# 2d_list_1.net
KiCad netlist of a schematic drawn in Altium Designer
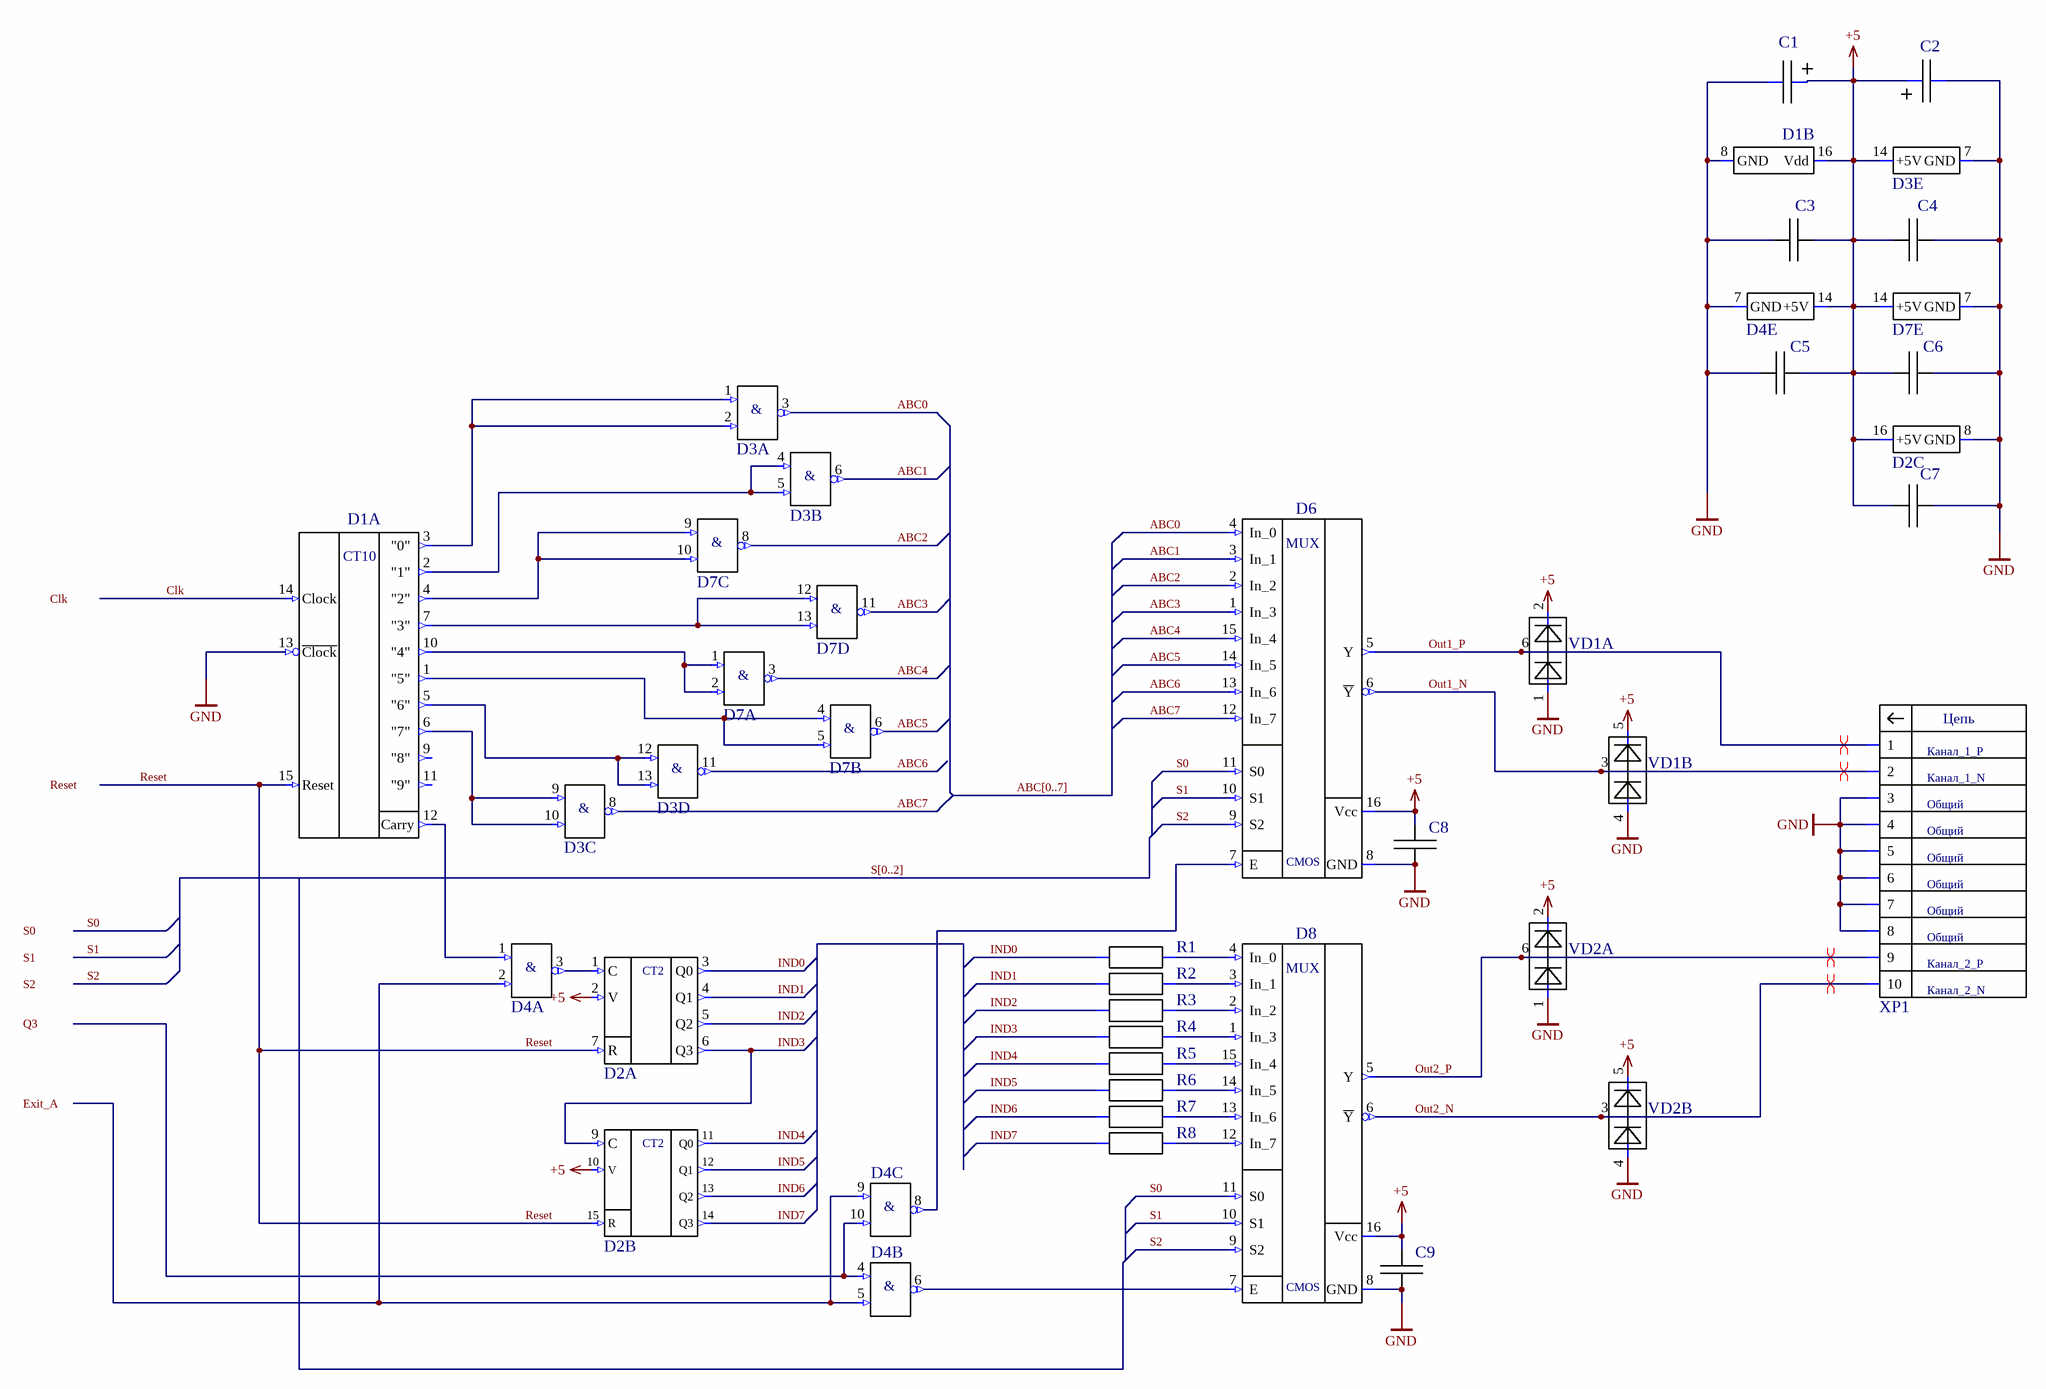
[diagram p0: 2d_list_1.schdoc]

(export (version "E")
  (design (tool "Eeschema 10.0.6"))
  (components
    (comp (ref "C1")
      (value "C")
      (footprint "C-Tantal")
      (description "К53-65 Конденсатор танталовый C(6032) 0,47-100 мкФ")
      (fields
        (field (name "MANUFACTURER") "ОАО \"Элеконд\"")
        (field (name "TOLERANCE") "10%")
        (field (name "CREATED_BY") "Желобаев")
      )
      (libsource (lib "Int_Library_for_Lessons_3") (part "K53-65_C_10%"))
    )
    (comp (ref "C2")
      (value "C")
      (footprint "C-Tantal")
      (description "К53-65 Конденсатор танталовый C(6032) 0,47-100 мкФ")
      (fields
        (field (name "MANUFACTURER") "ОАО \"Элеконд\"")
        (field (name "TOLERANCE") "10%")
        (field (name "CREATED_BY") "Желобаев")
      )
      (libsource (lib "Int_Library_for_Lessons_3") (part "K53-65_C_10%"))
    )
    (comp (ref "C3")
      (value "1206")
      (footprint "K10-79_3.2_1.6(1206)")
      (description "Чип конденсатор 1206 Н90 ряд Е6")
      (fields (field (name "MANUFACTURER") "ООО \"Кулон\"") (field (name "TOLERANCE") "+80%-20%"))
      (libsource (lib "Int_Library_for_Lessons_3") (part "К10-79_1206_Н90"))
    )
    (comp (ref "C4")
      (value "1206")
      (footprint "K10-79_3.2_1.6(1206)")
      (description "Чип конденсатор 1206 Н90 ряд Е6")
      (fields (field (name "MANUFACTURER") "ООО \"Кулон\"") (field (name "TOLERANCE") "+80%-20%"))
      (libsource (lib "Int_Library_for_Lessons_3") (part "К10-79_1206_Н90"))
    )
    (comp (ref "C5")
      (value "1206")
      (footprint "K10-79_3.2_1.6(1206)")
      (description "Чип конденсатор 1206 Н90 ряд Е6")
      (fields (field (name "MANUFACTURER") "ООО \"Кулон\"") (field (name "TOLERANCE") "+80%-20%"))
      (libsource (lib "Int_Library_for_Lessons_3") (part "К10-79_1206_Н90"))
    )
    (comp (ref "C6")
      (value "1206")
      (footprint "K10-79_3.2_1.6(1206)")
      (description "Чип конденсатор 1206 Н90 ряд Е6")
      (fields (field (name "MANUFACTURER") "ООО \"Кулон\"") (field (name "TOLERANCE") "+80%-20%"))
      (libsource (lib "Int_Library_for_Lessons_3") (part "К10-79_1206_Н90"))
    )
    (comp (ref "C7")
      (value "1206")
      (footprint "K10-79_3.2_1.6(1206)")
      (description "Чип конденсатор 1206 Н90 ряд Е6")
      (fields (field (name "MANUFACTURER") "ООО \"Кулон\"") (field (name "TOLERANCE") "+80%-20%"))
      (libsource (lib "Int_Library_for_Lessons_3") (part "К10-79_1206_Н90"))
    )
    (comp (ref "C8")
      (value "1206")
      (footprint "K10-79_3.2_1.6(1206)")
      (description "Чип конденсатор 1206 МП0 ряд Е24")
      (fields (field (name "MANUFACTURER") "ООО \"Кулон\"") (field (name "TOLERANCE") "±5%"))
      (libsource (lib "Int_Library_for_Lessons_3") (part "К10-79_1206_МП0"))
    )
    (comp (ref "C9")
      (value "1206")
      (footprint "K10-79_3.2_1.6(1206)")
      (description "Чип конденсатор 1206 МП0 ряд Е24")
      (fields (field (name "MANUFACTURER") "ООО \"Кулон\"") (field (name "TOLERANCE") "±5%"))
      (libsource (lib "Int_Library_for_Lessons_3") (part "К10-79_1206_МП0"))
    )
    (comp (ref "D1")
      (value "DIP-16")
      (footprint "DIP16")
      (description "Декадный счетчик c 10 декодированными выходами")
      (fields (field (name "MANUFACTURER") "STMicroelectronics") (field (name "CREATED_BY") "Желобаев"))
      (libsource (lib "Int_Library_for_Lessons_3") (part "HCF4017BEY"))
    )
    (comp (ref "D2")
      (value "~")
      (footprint "DIP16")
      (description "Два двоичных счетчика")
      (fields (field (name "MANUFACTURER") "Motorola") (field (name "CREATED_BY") "Желобаев"))
      (libsource (lib "Int_Library_for_Lessons_3") (part "MC14520BCP"))
    )
    (comp (ref "D3")
      (value "74AC00PC")
      (footprint "DIP14")
      (description "4 элемента 2И-НЕ TTL PDIP-14")
      (fields (field (name "MANUFACTURER") "ON Semiconductor") (field (name "CREATED_BY") "Желобаев"))
      (libsource (lib "Int_Library_for_Lessons_3") (part "74AC00PC"))
    )
    (comp (ref "D4")
      (value "74AC00PC")
      (footprint "DIP14")
      (description "4 элемента 2И-НЕ TTL PDIP-14")
      (fields (field (name "MANUFACTURER") "ON Semiconductor") (field (name "CREATED_BY") "Желобаев"))
      (libsource (lib "Int_Library_for_Lessons_3") (part "74AC00PC"))
    )
    (comp (ref "D6")
      (value "DIP-16")
      (footprint "DIP16")
      (description "мультиплексор 8 канальный CMOS")
      (fields (field (name "MANUFACTURER") "NXP Semiconductors") (field (name "CREATED_BY") "Желобаев"))
      (libsource (lib "Int_Library_for_Lessons_3") (part "74HC151N"))
    )
    (comp (ref "D7")
      (value "74AC00PC")
      (footprint "DIP14")
      (description "4 элемента 2И-НЕ TTL PDIP-14")
      (fields (field (name "MANUFACTURER") "ON Semiconductor") (field (name "CREATED_BY") "Желобаев"))
      (libsource (lib "Int_Library_for_Lessons_3") (part "74AC00PC"))
    )
    (comp (ref "D8")
      (value "DIP-16")
      (footprint "DIP16")
      (description "мультиплексор 8 канальный CMOS")
      (fields (field (name "MANUFACTURER") "NXP Semiconductors") (field (name "CREATED_BY") "Желобаев"))
      (libsource (lib "Int_Library_for_Lessons_3") (part "74HC151N"))
    )
    (comp (ref "R1")
      (value "~")
      (footprint "RES_0603_1608_N")
      (description "Резистор от 0,75 Ом до 10 МОм")
      (fields
        (field (name "MANUFACTURER") "ОАО \"НПО \"Эркон\"")
        (field (name "TOLERANCE") "5%")
        (field (name "CREATED_BY") "Желобаев")
      )
      (libsource (lib "Int_Library_for_Lessons_3") (part "Р1-12-0,1-5%"))
    )
    (comp (ref "R2")
      (value "~")
      (footprint "RES_0603_1608_N")
      (description "Резистор от 0,75 Ом до 10 МОм")
      (fields
        (field (name "MANUFACTURER") "ОАО \"НПО \"Эркон\"")
        (field (name "TOLERANCE") "5%")
        (field (name "CREATED_BY") "Желобаев")
      )
      (libsource (lib "Int_Library_for_Lessons_3") (part "Р1-12-0,1-5%"))
    )
    (comp (ref "R3")
      (value "~")
      (footprint "RES_0603_1608_N")
      (description "Резистор от 0,75 Ом до 10 МОм")
      (fields
        (field (name "MANUFACTURER") "ОАО \"НПО \"Эркон\"")
        (field (name "TOLERANCE") "5%")
        (field (name "CREATED_BY") "Желобаев")
      )
      (libsource (lib "Int_Library_for_Lessons_3") (part "Р1-12-0,1-5%"))
    )
    (comp (ref "R4")
      (value "~")
      (footprint "RES_0603_1608_N")
      (description "Резистор от 0,75 Ом до 10 МОм")
      (fields
        (field (name "MANUFACTURER") "ОАО \"НПО \"Эркон\"")
        (field (name "TOLERANCE") "5%")
        (field (name "CREATED_BY") "Желобаев")
      )
      (libsource (lib "Int_Library_for_Lessons_3") (part "Р1-12-0,1-5%"))
    )
    (comp (ref "R5")
      (value "~")
      (footprint "RES_0603_1608_N")
      (description "Резистор от 0,75 Ом до 10 МОм")
      (fields
        (field (name "MANUFACTURER") "ОАО \"НПО \"Эркон\"")
        (field (name "TOLERANCE") "5%")
        (field (name "CREATED_BY") "Желобаев")
      )
      (libsource (lib "Int_Library_for_Lessons_3") (part "Р1-12-0,1-5%"))
    )
    (comp (ref "R6")
      (value "~")
      (footprint "RES_0603_1608_N")
      (description "Резистор от 0,75 Ом до 10 МОм")
      (fields
        (field (name "MANUFACTURER") "ОАО \"НПО \"Эркон\"")
        (field (name "TOLERANCE") "5%")
        (field (name "CREATED_BY") "Желобаев")
      )
      (libsource (lib "Int_Library_for_Lessons_3") (part "Р1-12-0,1-5%"))
    )
    (comp (ref "R7")
      (value "~")
      (footprint "RES_0603_1608_N")
      (description "Резистор от 0,75 Ом до 10 МОм")
      (fields
        (field (name "MANUFACTURER") "ОАО \"НПО \"Эркон\"")
        (field (name "TOLERANCE") "5%")
        (field (name "CREATED_BY") "Желобаев")
      )
      (libsource (lib "Int_Library_for_Lessons_3") (part "Р1-12-0,1-5%"))
    )
    (comp (ref "R8")
      (value "~")
      (footprint "RES_0603_1608_N")
      (description "Резистор от 0,75 Ом до 10 МОм")
      (fields
        (field (name "MANUFACTURER") "ОАО \"НПО \"Эркон\"")
        (field (name "TOLERANCE") "5%")
        (field (name "CREATED_BY") "Желобаев")
      )
      (libsource (lib "Int_Library_for_Lessons_3") (part "Р1-12-0,1-5%"))
    )
    (comp (ref "VD1")
      (value "SOT-363")
      (footprint "SOT363_NXP")
      (description "Высокоскоростные, переключающие диоды")
      (fields
        (field (name "MANUFACTURER") "Nexperia")
        (field (name "VOLTAGE") "100")
        (field (name "CREATED_BY") "Желобаев")
      )
      (libsource (lib "Int_Library_for_Lessons_3") (part "BAV99S"))
    )
    (comp (ref "VD2")
      (value "SOT-363")
      (footprint "SOT363_NXP")
      (description "Высокоскоростные, переключающие диоды")
      (fields
        (field (name "MANUFACTURER") "Nexperia")
        (field (name "VOLTAGE") "100")
        (field (name "CREATED_BY") "Желобаев")
      )
      (libsource (lib "Int_Library_for_Lessons_3") (part "BAV99S"))
    )
    (comp (ref "XP1")
      (value "TE_1-1634689-0")
      (footprint "BH-10R")
      (description "Вилка типа BH-10R угловая правая двухрядная 2х5х2.54")
      (fields (field (name "MANUFACTURER") "TE Connectivity") (field (name "CREATED_BY") "Желобаев"))
      (libsource (lib "Int_Library_for_Lessons_3") (part "TE_1-1634689-0"))
    )
  )
  (nets
    (net (code "1") (name "+5") (class "Default")
      (node (ref "C1") (pin "+") (pinfunction "+_+") (pintype "passive"))
      (node (ref "C2") (pin "+") (pinfunction "+_+") (pintype "passive"))
      (node (ref "C3") (pin "2") (pinfunction "2_2") (pintype "passive"))
      (node (ref "C4") (pin "1") (pinfunction "1_1") (pintype "passive"))
      (node (ref "C5") (pin "2") (pinfunction "2_2") (pintype "passive"))
      (node (ref "C6") (pin "1") (pinfunction "1_1") (pintype "passive"))
      (node (ref "C7") (pin "1") (pinfunction "1_1") (pintype "passive"))
      (node (ref "C8") (pin "1") (pinfunction "1_1") (pintype "passive"))
      (node (ref "C9") (pin "1") (pinfunction "1_1") (pintype "passive"))
      (node (ref "D1") (pin "16") (pinfunction "Vdd_16") (pintype "power_in"))
      (node (ref "D2") (pin "10") (pinfunction "V_10") (pintype "input"))
      (node (ref "D2") (pin "16") (pinfunction "+5V_16") (pintype "power_in"))
      (node (ref "D2") (pin "2") (pinfunction "V_2") (pintype "input"))
      (node (ref "D3") (pin "14") (pinfunction "+5V_14") (pintype "power_in"))
      (node (ref "D4") (pin "14") (pinfunction "+5V_14") (pintype "power_in"))
      (node (ref "D6") (pin "16") (pinfunction "Vcc_16") (pintype "power_in"))
      (node (ref "D7") (pin "14") (pinfunction "+5V_14") (pintype "power_in"))
      (node (ref "D8") (pin "16") (pinfunction "Vcc_16") (pintype "power_in"))
      (node (ref "VD1") (pin "2") (pinfunction "K2_2") (pintype "passive"))
      (node (ref "VD1") (pin "5") (pinfunction "K4_5") (pintype "passive"))
      (node (ref "VD2") (pin "2") (pinfunction "K2_2") (pintype "passive"))
      (node (ref "VD2") (pin "5") (pinfunction "K4_5") (pintype "passive"))
    )
    (net (code "2") (name "/ABC0") (class "Default")
      (node (ref "D3") (pin "3") (pinfunction "Out_3") (pintype "output"))
      (node (ref "D6") (pin "4") (pinfunction "In_0_4") (pintype "input"))
    )
    (net (code "3") (name "/ABC1") (class "Default")
      (node (ref "D3") (pin "6") (pinfunction "Out_6") (pintype "output"))
      (node (ref "D6") (pin "3") (pinfunction "In_1_3") (pintype "input"))
    )
    (net (code "4") (name "/ABC2") (class "Default")
      (node (ref "D6") (pin "2") (pinfunction "In_2_2") (pintype "input"))
      (node (ref "D7") (pin "8") (pinfunction "Out_8") (pintype "output"))
    )
    (net (code "5") (name "/ABC3") (class "Default")
      (node (ref "D6") (pin "1") (pinfunction "In_3_1") (pintype "input"))
      (node (ref "D7") (pin "11") (pinfunction "Out_11") (pintype "output"))
    )
    (net (code "6") (name "/ABC4") (class "Default")
      (node (ref "D6") (pin "15") (pinfunction "In_4_15") (pintype "input"))
      (node (ref "D7") (pin "3") (pinfunction "Out_3") (pintype "output"))
    )
    (net (code "7") (name "/ABC5") (class "Default")
      (node (ref "D6") (pin "14") (pinfunction "In_5_14") (pintype "input"))
      (node (ref "D7") (pin "6") (pinfunction "Out_6") (pintype "output"))
    )
    (net (code "8") (name "/ABC6") (class "Default")
      (node (ref "D3") (pin "11") (pinfunction "Out_11") (pintype "output"))
      (node (ref "D6") (pin "13") (pinfunction "In_6_13") (pintype "input"))
    )
    (net (code "9") (name "/ABC7") (class "Default")
      (node (ref "D3") (pin "8") (pinfunction "Out_8") (pintype "output"))
      (node (ref "D6") (pin "12") (pinfunction "In_7_12") (pintype "input"))
    )
    (net (code "11") (name "/Clk") (class "Default")
      (node (ref "D1") (pin "14") (pinfunction "Clock_14") (pintype "input"))
    )
    (net (code "12") (name "/Exit_A") (class "Default")
      (node (ref "D4") (pin "2") (pinfunction "In2_2") (pintype "input"))
      (node (ref "D4") (pin "5") (pinfunction "In2_5") (pintype "input"))
      (node (ref "D4") (pin "9") (pinfunction "In1_9") (pintype "input"))
    )
    (net (code "13") (name "/IND0") (class "Default")
      (node (ref "D2") (pin "3") (pinfunction "Q0_3") (pintype "output"))
      (node (ref "R1") (pin "1") (pinfunction "1_1") (pintype "passive"))
    )
    (net (code "14") (name "/IND1") (class "Default")
      (node (ref "D2") (pin "4") (pinfunction "Q1_4") (pintype "output"))
      (node (ref "R2") (pin "1") (pinfunction "1_1") (pintype "passive"))
    )
    (net (code "15") (name "/IND2") (class "Default")
      (node (ref "D2") (pin "5") (pinfunction "Q2_5") (pintype "output"))
      (node (ref "R3") (pin "1") (pinfunction "1_1") (pintype "passive"))
    )
    (net (code "16") (name "/IND3") (class "Default")
      (node (ref "D2") (pin "6") (pinfunction "Q3_6") (pintype "output"))
      (node (ref "D2") (pin "9") (pinfunction "C_9") (pintype "input"))
      (node (ref "R4") (pin "1") (pinfunction "1_1") (pintype "passive"))
    )
    (net (code "17") (name "/IND4") (class "Default")
      (node (ref "D2") (pin "11") (pinfunction "Q0_11") (pintype "output"))
      (node (ref "R5") (pin "1") (pinfunction "1_1") (pintype "passive"))
    )
    (net (code "18") (name "/IND5") (class "Default")
      (node (ref "D2") (pin "12") (pinfunction "Q1_12") (pintype "output"))
      (node (ref "R6") (pin "1") (pinfunction "1_1") (pintype "passive"))
    )
    (net (code "19") (name "/IND6") (class "Default")
      (node (ref "D2") (pin "13") (pinfunction "Q2_13") (pintype "output"))
      (node (ref "R7") (pin "1") (pinfunction "1_1") (pintype "passive"))
    )
    (net (code "20") (name "/IND7") (class "Default")
      (node (ref "D2") (pin "14") (pinfunction "Q3_14") (pintype "output"))
      (node (ref "R8") (pin "1") (pinfunction "1_1") (pintype "passive"))
    )
    (net (code "21") (name "/Out1_N") (class "Default")
      (node (ref "D6") (pin "6") (pinfunction "Y_6") (pintype "output"))
      (node (ref "VD1") (pin "3") (pinfunction "K3A4_3") (pintype "passive"))
      (node (ref "XP1") (pin "2") (pinfunction "2_2") (pintype "passive"))
    )
    (net (code "22") (name "/Out1_P") (class "Default")
      (node (ref "D6") (pin "5") (pinfunction "Y_5") (pintype "output"))
      (node (ref "VD1") (pin "6") (pinfunction "K1A2_6") (pintype "passive"))
      (node (ref "XP1") (pin "1") (pinfunction "1_1") (pintype "passive"))
    )
    (net (code "23") (name "/Out2_N") (class "Default")
      (node (ref "D8") (pin "6") (pinfunction "Y_6") (pintype "output"))
      (node (ref "VD2") (pin "3") (pinfunction "K3A4_3") (pintype "passive"))
      (node (ref "XP1") (pin "10") (pinfunction "10_10") (pintype "passive"))
    )
    (net (code "24") (name "/Out2_P") (class "Default")
      (node (ref "D8") (pin "5") (pinfunction "Y_5") (pintype "output"))
      (node (ref "VD2") (pin "6") (pinfunction "K1A2_6") (pintype "passive"))
      (node (ref "XP1") (pin "9") (pinfunction "9_9") (pintype "passive"))
    )
    (net (code "25") (name "/Q3") (class "Default")
      (node (ref "D4") (pin "10") (pinfunction "In2_10") (pintype "input"))
      (node (ref "D4") (pin "4") (pinfunction "In1_4") (pintype "input"))
    )
    (net (code "26") (name "/Reset") (class "Default")
      (node (ref "D1") (pin "15") (pinfunction "Reset_15") (pintype "input"))
      (node (ref "D2") (pin "15") (pinfunction "R_15") (pintype "input"))
      (node (ref "D2") (pin "7") (pinfunction "R_7") (pintype "input"))
    )
    (net (code "27") (name "/S0") (class "Default")
      (node (ref "D6") (pin "11") (pinfunction "S0_11") (pintype "input"))
      (node (ref "D8") (pin "11") (pinfunction "S0_11") (pintype "input"))
    )
    (net (code "28") (name "/S1") (class "Default")
      (node (ref "D6") (pin "10") (pinfunction "S1_10") (pintype "input"))
      (node (ref "D8") (pin "10") (pinfunction "S1_10") (pintype "input"))
    )
    (net (code "29") (name "/S2") (class "Default")
      (node (ref "D6") (pin "9") (pinfunction "S2_9") (pintype "input"))
      (node (ref "D8") (pin "9") (pinfunction "S2_9") (pintype "input"))
    )
    (net (code "31") (name "GND") (class "Default")
      (node (ref "C1") (pin "-") (pinfunction "-_-") (pintype "passive"))
      (node (ref "C2") (pin "-") (pinfunction "-_-") (pintype "passive"))
      (node (ref "C3") (pin "1") (pinfunction "1_1") (pintype "passive"))
      (node (ref "C4") (pin "2") (pinfunction "2_2") (pintype "passive"))
      (node (ref "C5") (pin "1") (pinfunction "1_1") (pintype "passive"))
      (node (ref "C6") (pin "2") (pinfunction "2_2") (pintype "passive"))
      (node (ref "C7") (pin "2") (pinfunction "2_2") (pintype "passive"))
      (node (ref "C8") (pin "2") (pinfunction "2_2") (pintype "passive"))
      (node (ref "C9") (pin "2") (pinfunction "2_2") (pintype "passive"))
      (node (ref "D1") (pin "13") (pinfunction "Clock_13") (pintype "input"))
      (node (ref "D1") (pin "8") (pinfunction "GND_8") (pintype "power_in"))
      (node (ref "D2") (pin "8") (pinfunction "GND_8") (pintype "power_in"))
      (node (ref "D3") (pin "7") (pinfunction "GND_7") (pintype "power_in"))
      (node (ref "D4") (pin "7") (pinfunction "GND_7") (pintype "power_in"))
      (node (ref "D6") (pin "8") (pinfunction "GND_8") (pintype "power_in"))
      (node (ref "D7") (pin "7") (pinfunction "GND_7") (pintype "power_in"))
      (node (ref "D8") (pin "8") (pinfunction "GND_8") (pintype "power_in"))
      (node (ref "VD1") (pin "1") (pinfunction "A1_1") (pintype "passive"))
      (node (ref "VD1") (pin "4") (pinfunction "A3_4") (pintype "passive"))
      (node (ref "VD2") (pin "1") (pinfunction "A1_1") (pintype "passive"))
      (node (ref "VD2") (pin "4") (pinfunction "A3_4") (pintype "passive"))
      (node (ref "XP1") (pin "3") (pinfunction "3_3") (pintype "passive"))
      (node (ref "XP1") (pin "4") (pinfunction "4_4") (pintype "passive"))
      (node (ref "XP1") (pin "5") (pinfunction "5_5") (pintype "passive"))
      (node (ref "XP1") (pin "6") (pinfunction "6_6") (pintype "passive"))
      (node (ref "XP1") (pin "7") (pinfunction "7_7") (pintype "passive"))
      (node (ref "XP1") (pin "8") (pinfunction "8_8") (pintype "passive"))
    )
    (net (code "32") (name "Net-(D1A-\"0\")") (class "Default")
      (node (ref "D1") (pin "3") (pinfunction "\"0\"_3") (pintype "output"))
      (node (ref "D3") (pin "1") (pinfunction "In1_1") (pintype "input"))
      (node (ref "D3") (pin "2") (pinfunction "In2_2") (pintype "input"))
    )
    (net (code "33") (name "Net-(D1A-\"1\")") (class "Default")
      (node (ref "D1") (pin "2") (pinfunction "\"1\"_2") (pintype "output"))
      (node (ref "D3") (pin "4") (pinfunction "In1_4") (pintype "input"))
      (node (ref "D3") (pin "5") (pinfunction "In2_5") (pintype "input"))
    )
    (net (code "34") (name "Net-(D1A-\"2\")") (class "Default")
      (node (ref "D1") (pin "4") (pinfunction "\"2\"_4") (pintype "output"))
      (node (ref "D7") (pin "10") (pinfunction "In2_10") (pintype "input"))
      (node (ref "D7") (pin "9") (pinfunction "In1_9") (pintype "input"))
    )
    (net (code "35") (name "Net-(D1A-\"3\")") (class "Default")
      (node (ref "D1") (pin "7") (pinfunction "\"3\"_7") (pintype "output"))
      (node (ref "D7") (pin "12") (pinfunction "In1_12") (pintype "input"))
      (node (ref "D7") (pin "13") (pinfunction "In2_13") (pintype "input"))
    )
    (net (code "36") (name "Net-(D1A-\"4\")") (class "Default")
      (node (ref "D1") (pin "10") (pinfunction "\"4\"_10") (pintype "output"))
      (node (ref "D7") (pin "1") (pinfunction "In1_1") (pintype "input"))
      (node (ref "D7") (pin "2") (pinfunction "In2_2") (pintype "input"))
    )
    (net (code "37") (name "Net-(D1A-\"5\")") (class "Default")
      (node (ref "D1") (pin "1") (pinfunction "\"5\"_1") (pintype "output"))
      (node (ref "D7") (pin "4") (pinfunction "In1_4") (pintype "input"))
      (node (ref "D7") (pin "5") (pinfunction "In2_5") (pintype "input"))
    )
    (net (code "38") (name "Net-(D1A-\"6\")") (class "Default")
      (node (ref "D1") (pin "5") (pinfunction "\"6\"_5") (pintype "output"))
      (node (ref "D3") (pin "12") (pinfunction "In1_12") (pintype "input"))
      (node (ref "D3") (pin "13") (pinfunction "In2_13") (pintype "input"))
    )
    (net (code "39") (name "Net-(D1A-\"7\")") (class "Default")
      (node (ref "D1") (pin "6") (pinfunction "\"7\"_6") (pintype "output"))
      (node (ref "D3") (pin "10") (pinfunction "In2_10") (pintype "input"))
      (node (ref "D3") (pin "9") (pinfunction "In1_9") (pintype "input"))
    )
    (net (code "40") (name "Net-(D1A-Carry)") (class "Default")
      (node (ref "D1") (pin "12") (pinfunction "Carry_12") (pintype "output"))
      (node (ref "D4") (pin "1") (pinfunction "In1_1") (pintype "input"))
    )
    (net (code "41") (name "Net-(D2A-C)") (class "Default")
      (node (ref "D2") (pin "1") (pinfunction "C_1") (pintype "input"))
      (node (ref "D4") (pin "3") (pinfunction "Out_3") (pintype "output"))
    )
    (net (code "42") (name "Net-(D4B-Out)") (class "Default")
      (node (ref "D4") (pin "6") (pinfunction "Out_6") (pintype "output"))
      (node (ref "D8") (pin "7") (pinfunction "E_7") (pintype "input"))
    )
    (net (code "43") (name "Net-(D4C-Out)") (class "Default")
      (node (ref "D4") (pin "8") (pinfunction "Out_8") (pintype "output"))
      (node (ref "D6") (pin "7") (pinfunction "E_7") (pintype "input"))
    )
    (net (code "44") (name "Net-(D8-In_0)") (class "Default")
      (node (ref "D8") (pin "4") (pinfunction "In_0_4") (pintype "input"))
      (node (ref "R1") (pin "2") (pinfunction "2_2") (pintype "passive"))
    )
    (net (code "45") (name "Net-(D8-In_1)") (class "Default")
      (node (ref "D8") (pin "3") (pinfunction "In_1_3") (pintype "input"))
      (node (ref "R2") (pin "2") (pinfunction "2_2") (pintype "passive"))
    )
    (net (code "46") (name "Net-(D8-In_2)") (class "Default")
      (node (ref "D8") (pin "2") (pinfunction "In_2_2") (pintype "input"))
      (node (ref "R3") (pin "2") (pinfunction "2_2") (pintype "passive"))
    )
    (net (code "47") (name "Net-(D8-In_3)") (class "Default")
      (node (ref "D8") (pin "1") (pinfunction "In_3_1") (pintype "input"))
      (node (ref "R4") (pin "2") (pinfunction "2_2") (pintype "passive"))
    )
    (net (code "48") (name "Net-(D8-In_4)") (class "Default")
      (node (ref "D8") (pin "15") (pinfunction "In_4_15") (pintype "input"))
      (node (ref "R5") (pin "2") (pinfunction "2_2") (pintype "passive"))
    )
    (net (code "49") (name "Net-(D8-In_5)") (class "Default")
      (node (ref "D8") (pin "14") (pinfunction "In_5_14") (pintype "input"))
      (node (ref "R6") (pin "2") (pinfunction "2_2") (pintype "passive"))
    )
    (net (code "50") (name "Net-(D8-In_6)") (class "Default")
      (node (ref "D8") (pin "13") (pinfunction "In_6_13") (pintype "input"))
      (node (ref "R7") (pin "2") (pinfunction "2_2") (pintype "passive"))
    )
    (net (code "51") (name "Net-(D8-In_7)") (class "Default")
      (node (ref "D8") (pin "12") (pinfunction "In_7_12") (pintype "input"))
      (node (ref "R8") (pin "2") (pinfunction "2_2") (pintype "passive"))
    )
    (net (code "52") (name "unconnected-(D1A-\"8\"-Pad9)") (class "Default")
      (node (ref "D1") (pin "9") (pinfunction "\"8\"_9") (pintype "output"))
    )
    (net (code "53") (name "unconnected-(D1A-\"9\"-Pad11)") (class "Default")
      (node (ref "D1") (pin "11") (pinfunction "\"9\"_11") (pintype "output"))
    )
  )
)
